# STM32F103RB.net
KiCad netlist of a schematic drawn in Altium Designer
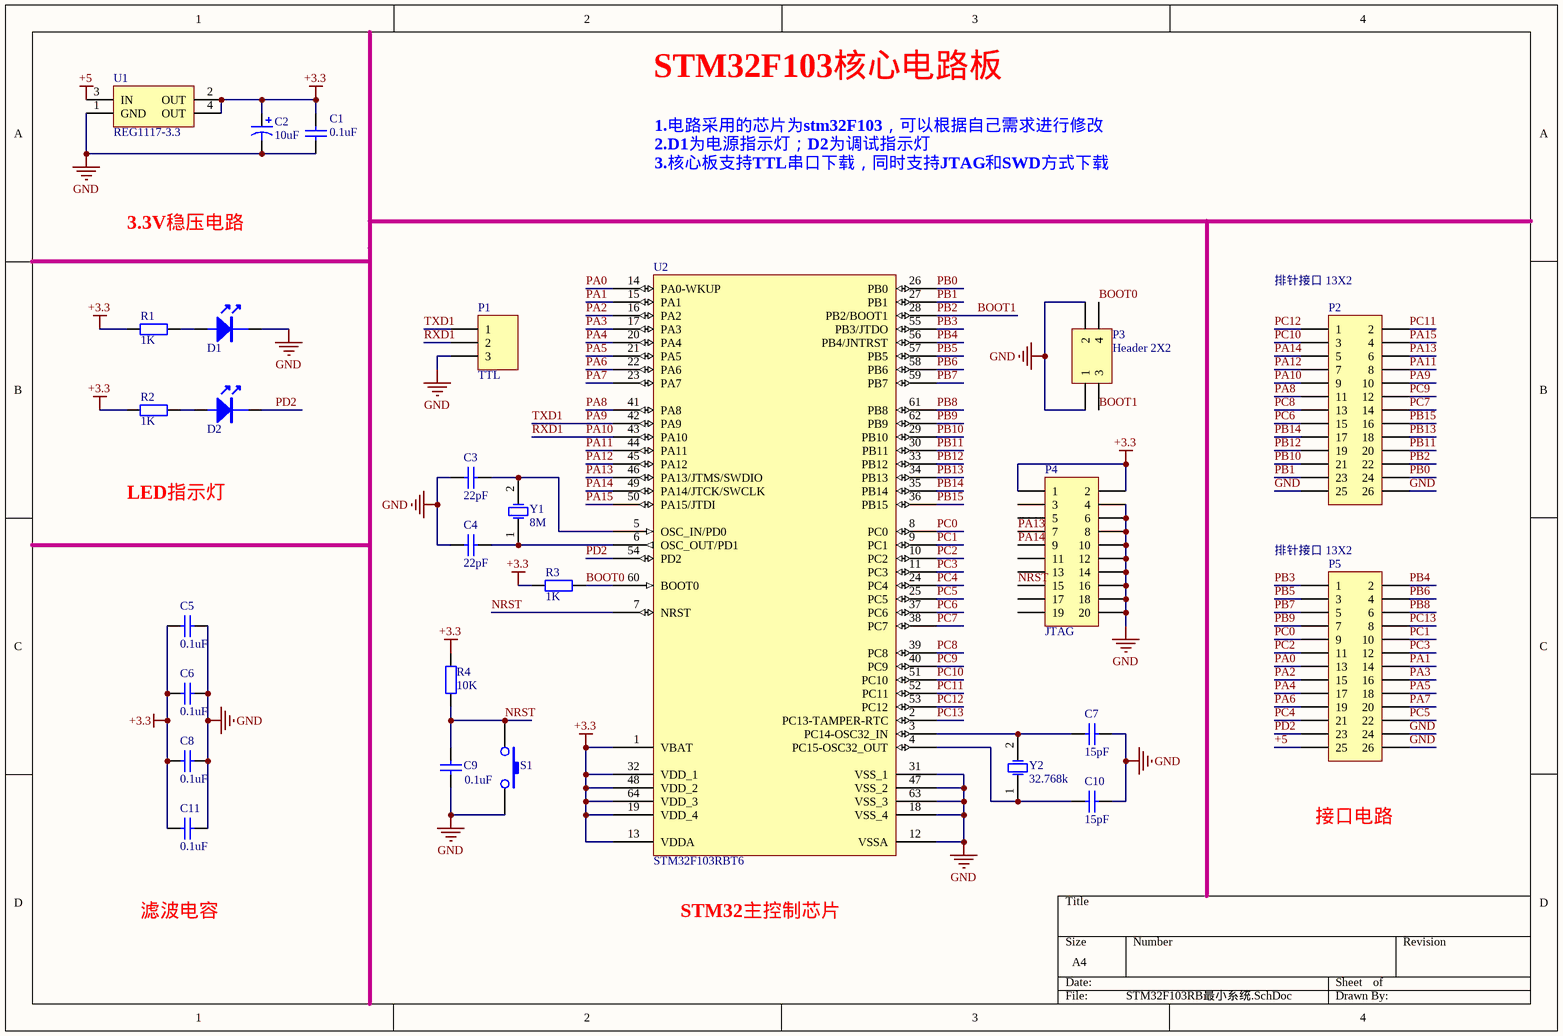
[diagram p0: STM32F103RB最小系统.SchDoc]

(export (version "E")
  (design (tool "Eeschema 10.0.6"))
  (components
    (comp (ref "C1")
      (value "0.1uF")
      (footprint "0805C")
      (description "Capacitor")
      (fields (field (name "PUBLISHER") "Altium Limited"))
      (libsource (lib "Miscellaneous Devices") (part "Cap"))
    )
    (comp (ref "C2")
      (value "10uF")
      (footprint "0805C")
      (description "Polarized Capacitor (Radial)")
      (fields (field (name "PUBLISHER") "Altium Limited"))
      (libsource (lib "Miscellaneous Devices") (part "Cap Pol1"))
    )
    (comp (ref "C3")
      (value "22pF")
      (footprint "0805C")
      (description "Capacitor")
      (fields (field (name "PUBLISHER") "Altium Limited"))
      (libsource (lib "Miscellaneous Devices") (part "Cap"))
    )
    (comp (ref "C4")
      (value "22pF")
      (footprint "0805C")
      (description "Capacitor")
      (fields (field (name "PUBLISHER") "Altium Limited"))
      (libsource (lib "Miscellaneous Devices") (part "Cap"))
    )
    (comp (ref "C5")
      (value "0.1uF")
      (footprint "0805C")
      (description "Capacitor")
      (fields (field (name "PUBLISHER") "Altium Limited"))
      (libsource (lib "Miscellaneous Devices") (part "Cap"))
    )
    (comp (ref "C6")
      (value "0.1uF")
      (footprint "0805C")
      (description "Capacitor")
      (fields (field (name "PUBLISHER") "Altium Limited"))
      (libsource (lib "Miscellaneous Devices") (part "Cap"))
    )
    (comp (ref "C7")
      (value "15pF")
      (footprint "0805C")
      (description "Capacitor")
      (fields (field (name "PUBLISHER") "Altium Limited"))
      (libsource (lib "Miscellaneous Devices") (part "Cap"))
    )
    (comp (ref "C8")
      (value "0.1uF")
      (footprint "0805C")
      (description "Capacitor")
      (fields (field (name "PUBLISHER") "Altium Limited"))
      (libsource (lib "Miscellaneous Devices") (part "Cap"))
    )
    (comp (ref "C9")
      (value "0.1uF")
      (footprint "0805C")
      (description "Capacitor")
      (fields (field (name "PUBLISHER") "Altium Limited"))
      (libsource (lib "Miscellaneous Devices") (part "Cap"))
    )
    (comp (ref "C10")
      (value "15pF")
      (footprint "0805C")
      (description "Capacitor")
      (fields (field (name "PUBLISHER") "Altium Limited"))
      (libsource (lib "Miscellaneous Devices") (part "Cap"))
    )
    (comp (ref "C11")
      (value "0.1uF")
      (footprint "0805C")
      (description "Capacitor")
      (fields (field (name "PUBLISHER") "Altium Limited"))
      (libsource (lib "Miscellaneous Devices") (part "Cap"))
    )
    (comp (ref "D1") (value "LED") (footprint "LED0805") (libsource (lib "CCDXPLIB") (part "LED")))
    (comp (ref "D2") (value "LED") (footprint "LED0805") (libsource (lib "CCDXPLIB") (part "LED")))
    (comp (ref "P1")
      (value "TTL")
      (footprint "HDR1X3")
      (description "Header, 3-Pin")
      (fields (field (name "PUBLISHER") "Altium Limited"))
      (libsource (lib "Miscellaneous Connectors") (part "Header 3"))
    )
    (comp (ref "P2")
      (value "排针接口 13X2")
      (footprint "HDR2X13")
      (description "Header, 13-Pin, Dual row")
      (fields (field (name "PUBLISHER") "Altium Limited"))
      (libsource (lib "Miscellaneous Connectors") (part "Header 13X2"))
    )
    (comp (ref "P3")
      (value "Header 2X2")
      (footprint "HDR2X2")
      (description "Header, 2-Pin, Dual row")
      (fields (field (name "PUBLISHER") "Altium Limited"))
      (libsource (lib "Miscellaneous Connectors") (part "Header 2X2"))
    )
    (comp (ref "P4")
      (value "JTAG")
      (footprint "JTAG20")
      (description "Header, 10-Pin, Dual row")
      (fields (field (name "PUBLISHER") "Altium Limited"))
      (libsource (lib "Miscellaneous Connectors") (part "Header 10X2"))
    )
    (comp (ref "P5")
      (value "排针接口 13X2")
      (footprint "HDR2X13")
      (description "Header, 13-Pin, Dual row")
      (fields (field (name "PUBLISHER") "Altium Limited"))
      (libsource (lib "Miscellaneous Connectors") (part "Header 13X2"))
    )
    (comp (ref "R1")
      (value "1K")
      (footprint "0805R")
      (description "Resistor")
      (fields (field (name "PUBLISHER") "Altium Limited"))
      (libsource (lib "Miscellaneous Devices") (part "Res2"))
    )
    (comp (ref "R2")
      (value "1K")
      (footprint "0805R")
      (description "Resistor")
      (fields (field (name "PUBLISHER") "Altium Limited"))
      (libsource (lib "Miscellaneous Devices") (part "Res2"))
    )
    (comp (ref "R3")
      (value "1K")
      (footprint "0805R")
      (description "Resistor")
      (fields (field (name "PUBLISHER") "Altium Limited"))
      (libsource (lib "Miscellaneous Devices") (part "Res2"))
    )
    (comp (ref "R4")
      (value "10K")
      (footprint "0805R")
      (description "Resistor")
      (fields (field (name "PUBLISHER") "Altium Limited"))
      (libsource (lib "") (part "Res2_1"))
    )
    (comp (ref "S1") (value "KEY") (footprint "KEY_SOP") (libsource (lib "CCDXPLIB") (part "KEY")))
    (comp (ref "U1")
      (value "REG1117-3.3")
      (footprint "ZZ311")
      (description "800mA and 1A Low Dropout Positive Regulator 2.85V, 3.3V, 5V, and Adjustable")
      (fields (field (name "PUBLISHER") "Altium Limited"))
      (libsource (lib "BB Power Mgt Voltage Regulator") (part "REG1117-3.3"))
    )
    (comp (ref "U2")
      (value "STM32F103RBT6")
      (footprint "LQFP64_N")
      (description "STM32 ARM-based 32-bit MCU with 128 Kbytes Flash, 64-pin LQFP, Industrial Temperature")
      (fields (field (name "PUBLISHER") "Altium Limited"))
      (libsource (lib "ST Microcontroller 32-Bit STM32") (part "STM32F103RBT6"))
    )
    (comp (ref "Y1")
      (value "8M")
      (footprint "OSC2PR-1")
      (description "Crystal Oscillator")
      (fields (field (name "PUBLISHER") "Altium Limited"))
      (libsource (lib "Miscellaneous Devices") (part "XTAL"))
    )
    (comp (ref "Y2")
      (value "32.768k")
      (footprint "XTAL-B")
      (description "Crystal Oscillator")
      (fields (field (name "PUBLISHER") "Altium Limited"))
      (libsource (lib "Miscellaneous Devices") (part "XTAL"))
    )
  )
  (nets
    (net (code "1") (name "+3.3") (class "Default")
      (node (ref "C1") (pin "2") (pinfunction "2_2") (pintype "passive"))
      (node (ref "C11") (pin "1") (pinfunction "1_1") (pintype "passive"))
      (node (ref "C2") (pin "1") (pinfunction "1_1") (pintype "passive"))
      (node (ref "C5") (pin "1") (pinfunction "1_1") (pintype "passive"))
      (node (ref "C6") (pin "1") (pinfunction "1_1") (pintype "passive"))
      (node (ref "C8") (pin "1") (pinfunction "1_1") (pintype "passive"))
      (node (ref "P4") (pin "1") (pinfunction "1_1") (pintype "passive"))
      (node (ref "P4") (pin "2") (pinfunction "2_2") (pintype "passive"))
      (node (ref "R1") (pin "1") (pinfunction "1_1") (pintype "passive"))
      (node (ref "R2") (pin "1") (pinfunction "1_1") (pintype "passive"))
      (node (ref "R3") (pin "1") (pinfunction "1_1") (pintype "passive"))
      (node (ref "R4") (pin "2") (pinfunction "2_2") (pintype "passive"))
      (node (ref "U1") (pin "2") (pinfunction "OUT_2") (pintype "power_in"))
      (node (ref "U1") (pin "4") (pinfunction "OUT_4") (pintype "power_in"))
      (node (ref "U2") (pin "1") (pinfunction "VBAT_1") (pintype "power_in"))
      (node (ref "U2") (pin "13") (pinfunction "VDDA_13") (pintype "power_in"))
      (node (ref "U2") (pin "19") (pinfunction "VDD_4_19") (pintype "power_in"))
      (node (ref "U2") (pin "32") (pinfunction "VDD_1_32") (pintype "power_in"))
      (node (ref "U2") (pin "48") (pinfunction "VDD_2_48") (pintype "power_in"))
      (node (ref "U2") (pin "64") (pinfunction "VDD_3_64") (pintype "power_in"))
    )
    (net (code "2") (name "+5") (class "Default")
      (node (ref "P5") (pin "25") (pinfunction "25_25") (pintype "passive"))
      (node (ref "U1") (pin "3") (pinfunction "IN_3") (pintype "power_in"))
    )
    (net (code "3") (name "/BOOT0") (class "Default")
      (node (ref "P3") (pin "4") (pinfunction "4_4") (pintype "passive"))
      (node (ref "R3") (pin "2") (pinfunction "2_2") (pintype "passive"))
      (node (ref "U2") (pin "60") (pinfunction "BOOT0_60") (pintype "input"))
    )
    (net (code "4") (name "/BOOT1") (class "Default")
      (node (ref "P2") (pin "22") (pinfunction "22_22") (pintype "passive"))
      (node (ref "P3") (pin "3") (pinfunction "3_3") (pintype "passive"))
      (node (ref "U2") (pin "28") (pinfunction "PB2/BOOT1_28") (pintype "bidirectional"))
    )
    (net (code "5") (name "/NRST") (class "Default")
      (node (ref "C9") (pin "2") (pinfunction "2_2") (pintype "passive"))
      (node (ref "P4") (pin "15") (pinfunction "15_15") (pintype "passive"))
      (node (ref "R4") (pin "1") (pinfunction "1_1") (pintype "passive"))
      (node (ref "S1") (pin "1") (pinfunction "1_1") (pintype "passive"))
      (node (ref "U2") (pin "7") (pinfunction "NRST_7") (pintype "bidirectional"))
    )
    (net (code "6") (name "/PA0") (class "Default")
      (node (ref "P5") (pin "13") (pinfunction "13_13") (pintype "passive"))
      (node (ref "U2") (pin "14") (pinfunction "PA0-WKUP_14") (pintype "bidirectional"))
    )
    (net (code "7") (name "/PA1") (class "Default")
      (node (ref "P5") (pin "14") (pinfunction "14_14") (pintype "passive"))
      (node (ref "U2") (pin "15") (pinfunction "PA1_15") (pintype "bidirectional"))
    )
    (net (code "8") (name "/PA2") (class "Default")
      (node (ref "P5") (pin "15") (pinfunction "15_15") (pintype "passive"))
      (node (ref "U2") (pin "16") (pinfunction "PA2_16") (pintype "bidirectional"))
    )
    (net (code "9") (name "/PA3") (class "Default")
      (node (ref "P5") (pin "16") (pinfunction "16_16") (pintype "passive"))
      (node (ref "U2") (pin "17") (pinfunction "PA3_17") (pintype "bidirectional"))
    )
    (net (code "10") (name "/PA4") (class "Default")
      (node (ref "P5") (pin "17") (pinfunction "17_17") (pintype "passive"))
      (node (ref "U2") (pin "20") (pinfunction "PA4_20") (pintype "bidirectional"))
    )
    (net (code "11") (name "/PA5") (class "Default")
      (node (ref "P5") (pin "18") (pinfunction "18_18") (pintype "passive"))
      (node (ref "U2") (pin "21") (pinfunction "PA5_21") (pintype "bidirectional"))
    )
    (net (code "12") (name "/PA6") (class "Default")
      (node (ref "P5") (pin "19") (pinfunction "19_19") (pintype "passive"))
      (node (ref "U2") (pin "22") (pinfunction "PA6_22") (pintype "bidirectional"))
    )
    (net (code "13") (name "/PA7") (class "Default")
      (node (ref "P5") (pin "20") (pinfunction "20_20") (pintype "passive"))
      (node (ref "U2") (pin "23") (pinfunction "PA7_23") (pintype "bidirectional"))
    )
    (net (code "14") (name "/PA8") (class "Default")
      (node (ref "P2") (pin "11") (pinfunction "11_11") (pintype "passive"))
      (node (ref "U2") (pin "41") (pinfunction "PA8_41") (pintype "bidirectional"))
    )
    (net (code "15") (name "/PA9") (class "Default")
      (node (ref "P1") (pin "1") (pinfunction "1_1") (pintype "passive"))
      (node (ref "P2") (pin "10") (pinfunction "10_10") (pintype "passive"))
      (node (ref "U2") (pin "42") (pinfunction "PA9_42") (pintype "bidirectional"))
    )
    (net (code "16") (name "/PA10") (class "Default")
      (node (ref "P1") (pin "2") (pinfunction "2_2") (pintype "passive"))
      (node (ref "P2") (pin "9") (pinfunction "9_9") (pintype "passive"))
      (node (ref "U2") (pin "43") (pinfunction "PA10_43") (pintype "bidirectional"))
    )
    (net (code "17") (name "/PA11") (class "Default")
      (node (ref "P2") (pin "8") (pinfunction "8_8") (pintype "passive"))
      (node (ref "U2") (pin "44") (pinfunction "PA11_44") (pintype "bidirectional"))
    )
    (net (code "18") (name "/PA12") (class "Default")
      (node (ref "P2") (pin "7") (pinfunction "7_7") (pintype "passive"))
      (node (ref "U2") (pin "45") (pinfunction "PA12_45") (pintype "bidirectional"))
    )
    (net (code "19") (name "/PA13") (class "Default")
      (node (ref "P2") (pin "6") (pinfunction "6_6") (pintype "passive"))
      (node (ref "P4") (pin "7") (pinfunction "7_7") (pintype "passive"))
      (node (ref "U2") (pin "46") (pinfunction "PA13/JTMS/SWDIO_46") (pintype "bidirectional"))
    )
    (net (code "20") (name "/PA14") (class "Default")
      (node (ref "P2") (pin "5") (pinfunction "5_5") (pintype "passive"))
      (node (ref "P4") (pin "9") (pinfunction "9_9") (pintype "passive"))
      (node (ref "U2") (pin "49") (pinfunction "PA14/JTCK/SWCLK_49") (pintype "bidirectional"))
    )
    (net (code "21") (name "/PA15") (class "Default")
      (node (ref "P2") (pin "4") (pinfunction "4_4") (pintype "passive"))
      (node (ref "U2") (pin "50") (pinfunction "PA15/JTDI_50") (pintype "bidirectional"))
    )
    (net (code "22") (name "/PB0") (class "Default")
      (node (ref "P2") (pin "24") (pinfunction "24_24") (pintype "passive"))
      (node (ref "U2") (pin "26") (pinfunction "PB0_26") (pintype "bidirectional"))
    )
    (net (code "23") (name "/PB1") (class "Default")
      (node (ref "P2") (pin "23") (pinfunction "23_23") (pintype "passive"))
      (node (ref "U2") (pin "27") (pinfunction "PB1_27") (pintype "bidirectional"))
    )
    (net (code "24") (name "/PB3") (class "Default")
      (node (ref "P5") (pin "1") (pinfunction "1_1") (pintype "passive"))
      (node (ref "U2") (pin "55") (pinfunction "PB3/JTDO_55") (pintype "bidirectional"))
    )
    (net (code "25") (name "/PB4") (class "Default")
      (node (ref "P5") (pin "2") (pinfunction "2_2") (pintype "passive"))
      (node (ref "U2") (pin "56") (pinfunction "PB4/JNTRST_56") (pintype "bidirectional"))
    )
    (net (code "26") (name "/PB5") (class "Default")
      (node (ref "P5") (pin "3") (pinfunction "3_3") (pintype "passive"))
      (node (ref "U2") (pin "57") (pinfunction "PB5_57") (pintype "bidirectional"))
    )
    (net (code "27") (name "/PB6") (class "Default")
      (node (ref "P5") (pin "4") (pinfunction "4_4") (pintype "passive"))
      (node (ref "U2") (pin "58") (pinfunction "PB6_58") (pintype "bidirectional"))
    )
    (net (code "28") (name "/PB7") (class "Default")
      (node (ref "P5") (pin "5") (pinfunction "5_5") (pintype "passive"))
      (node (ref "U2") (pin "59") (pinfunction "PB7_59") (pintype "bidirectional"))
    )
    (net (code "29") (name "/PB8") (class "Default")
      (node (ref "P5") (pin "6") (pinfunction "6_6") (pintype "passive"))
      (node (ref "U2") (pin "61") (pinfunction "PB8_61") (pintype "bidirectional"))
    )
    (net (code "30") (name "/PB9") (class "Default")
      (node (ref "P5") (pin "7") (pinfunction "7_7") (pintype "passive"))
      (node (ref "U2") (pin "62") (pinfunction "PB9_62") (pintype "bidirectional"))
    )
    (net (code "31") (name "/PB10") (class "Default")
      (node (ref "P2") (pin "21") (pinfunction "21_21") (pintype "passive"))
      (node (ref "U2") (pin "29") (pinfunction "PB10_29") (pintype "bidirectional"))
    )
    (net (code "32") (name "/PB11") (class "Default")
      (node (ref "P2") (pin "20") (pinfunction "20_20") (pintype "passive"))
      (node (ref "U2") (pin "30") (pinfunction "PB11_30") (pintype "bidirectional"))
    )
    (net (code "33") (name "/PB12") (class "Default")
      (node (ref "P2") (pin "19") (pinfunction "19_19") (pintype "passive"))
      (node (ref "U2") (pin "33") (pinfunction "PB12_33") (pintype "bidirectional"))
    )
    (net (code "34") (name "/PB13") (class "Default")
      (node (ref "P2") (pin "18") (pinfunction "18_18") (pintype "passive"))
      (node (ref "U2") (pin "34") (pinfunction "PB13_34") (pintype "bidirectional"))
    )
    (net (code "35") (name "/PB14") (class "Default")
      (node (ref "P2") (pin "17") (pinfunction "17_17") (pintype "passive"))
      (node (ref "U2") (pin "35") (pinfunction "PB14_35") (pintype "bidirectional"))
    )
    (net (code "36") (name "/PB15") (class "Default")
      (node (ref "P2") (pin "16") (pinfunction "16_16") (pintype "passive"))
      (node (ref "U2") (pin "36") (pinfunction "PB15_36") (pintype "bidirectional"))
    )
    (net (code "37") (name "/PC0") (class "Default")
      (node (ref "P5") (pin "9") (pinfunction "9_9") (pintype "passive"))
      (node (ref "U2") (pin "8") (pinfunction "PC0_8") (pintype "bidirectional"))
    )
    (net (code "38") (name "/PC1") (class "Default")
      (node (ref "P5") (pin "10") (pinfunction "10_10") (pintype "passive"))
      (node (ref "U2") (pin "9") (pinfunction "PC1_9") (pintype "bidirectional"))
    )
    (net (code "39") (name "/PC2") (class "Default")
      (node (ref "P5") (pin "11") (pinfunction "11_11") (pintype "passive"))
      (node (ref "U2") (pin "10") (pinfunction "PC2_10") (pintype "bidirectional"))
    )
    (net (code "40") (name "/PC3") (class "Default")
      (node (ref "P5") (pin "12") (pinfunction "12_12") (pintype "passive"))
      (node (ref "U2") (pin "11") (pinfunction "PC3_11") (pintype "bidirectional"))
    )
    (net (code "41") (name "/PC4") (class "Default")
      (node (ref "P5") (pin "21") (pinfunction "21_21") (pintype "passive"))
      (node (ref "U2") (pin "24") (pinfunction "PC4_24") (pintype "bidirectional"))
    )
    (net (code "42") (name "/PC5") (class "Default")
      (node (ref "P5") (pin "22") (pinfunction "22_22") (pintype "passive"))
      (node (ref "U2") (pin "25") (pinfunction "PC5_25") (pintype "bidirectional"))
    )
    (net (code "43") (name "/PC6") (class "Default")
      (node (ref "P2") (pin "15") (pinfunction "15_15") (pintype "passive"))
      (node (ref "U2") (pin "37") (pinfunction "PC6_37") (pintype "bidirectional"))
    )
    (net (code "44") (name "/PC7") (class "Default")
      (node (ref "P2") (pin "14") (pinfunction "14_14") (pintype "passive"))
      (node (ref "U2") (pin "38") (pinfunction "PC7_38") (pintype "bidirectional"))
    )
    (net (code "45") (name "/PC8") (class "Default")
      (node (ref "P2") (pin "13") (pinfunction "13_13") (pintype "passive"))
      (node (ref "U2") (pin "39") (pinfunction "PC8_39") (pintype "bidirectional"))
    )
    (net (code "46") (name "/PC9") (class "Default")
      (node (ref "P2") (pin "12") (pinfunction "12_12") (pintype "passive"))
      (node (ref "U2") (pin "40") (pinfunction "PC9_40") (pintype "bidirectional"))
    )
    (net (code "47") (name "/PC10") (class "Default")
      (node (ref "P2") (pin "3") (pinfunction "3_3") (pintype "passive"))
      (node (ref "U2") (pin "51") (pinfunction "PC10_51") (pintype "bidirectional"))
    )
    (net (code "48") (name "/PC11") (class "Default")
      (node (ref "P2") (pin "2") (pinfunction "2_2") (pintype "passive"))
      (node (ref "U2") (pin "52") (pinfunction "PC11_52") (pintype "bidirectional"))
    )
    (net (code "49") (name "/PC12") (class "Default")
      (node (ref "P2") (pin "1") (pinfunction "1_1") (pintype "passive"))
      (node (ref "U2") (pin "53") (pinfunction "PC12_53") (pintype "bidirectional"))
    )
    (net (code "50") (name "/PC13") (class "Default")
      (node (ref "P5") (pin "8") (pinfunction "8_8") (pintype "passive"))
      (node (ref "U2") (pin "2") (pinfunction "PC13-TAMPER-RTC_2") (pintype "bidirectional"))
    )
    (net (code "51") (name "/PD2") (class "Default")
      (node (ref "D2") (pin "2") (pinfunction "2_2") (pintype "passive"))
      (node (ref "P5") (pin "23") (pinfunction "23_23") (pintype "passive"))
      (node (ref "U2") (pin "54") (pinfunction "PD2_54") (pintype "bidirectional"))
    )
    (net (code "52") (name "GND") (class "Default")
      (node (ref "C1") (pin "1") (pinfunction "1_1") (pintype "passive"))
      (node (ref "C10") (pin "2") (pinfunction "2_2") (pintype "passive"))
      (node (ref "C11") (pin "2") (pinfunction "2_2") (pintype "passive"))
      (node (ref "C2") (pin "2") (pinfunction "2_2") (pintype "passive"))
      (node (ref "C3") (pin "1") (pinfunction "1_1") (pintype "passive"))
      (node (ref "C4") (pin "1") (pinfunction "1_1") (pintype "passive"))
      (node (ref "C5") (pin "2") (pinfunction "2_2") (pintype "passive"))
      (node (ref "C6") (pin "2") (pinfunction "2_2") (pintype "passive"))
      (node (ref "C7") (pin "2") (pinfunction "2_2") (pintype "passive"))
      (node (ref "C8") (pin "2") (pinfunction "2_2") (pintype "passive"))
      (node (ref "C9") (pin "1") (pinfunction "1_1") (pintype "passive"))
      (node (ref "D1") (pin "2") (pinfunction "2_2") (pintype "passive"))
      (node (ref "P1") (pin "3") (pinfunction "3_3") (pintype "passive"))
      (node (ref "P2") (pin "25") (pinfunction "25_25") (pintype "passive"))
      (node (ref "P2") (pin "26") (pinfunction "26_26") (pintype "passive"))
      (node (ref "P3") (pin "1") (pinfunction "1_1") (pintype "passive"))
      (node (ref "P3") (pin "2") (pinfunction "2_2") (pintype "passive"))
      (node (ref "P4") (pin "10") (pinfunction "10_10") (pintype "passive"))
      (node (ref "P4") (pin "12") (pinfunction "12_12") (pintype "passive"))
      (node (ref "P4") (pin "14") (pinfunction "14_14") (pintype "passive"))
      (node (ref "P4") (pin "16") (pinfunction "16_16") (pintype "passive"))
      (node (ref "P4") (pin "18") (pinfunction "18_18") (pintype "passive"))
      (node (ref "P4") (pin "20") (pinfunction "20_20") (pintype "passive"))
      (node (ref "P4") (pin "4") (pinfunction "4_4") (pintype "passive"))
      (node (ref "P4") (pin "6") (pinfunction "6_6") (pintype "passive"))
      (node (ref "P4") (pin "8") (pinfunction "8_8") (pintype "passive"))
      (node (ref "P5") (pin "24") (pinfunction "24_24") (pintype "passive"))
      (node (ref "P5") (pin "26") (pinfunction "26_26") (pintype "passive"))
      (node (ref "S1") (pin "2") (pinfunction "2_2") (pintype "passive"))
      (node (ref "U1") (pin "1") (pinfunction "GND_1") (pintype "power_in"))
      (node (ref "U2") (pin "12") (pinfunction "VSSA_12") (pintype "power_in"))
      (node (ref "U2") (pin "18") (pinfunction "VSS_4_18") (pintype "power_in"))
      (node (ref "U2") (pin "31") (pinfunction "VSS_1_31") (pintype "power_in"))
      (node (ref "U2") (pin "47") (pinfunction "VSS_2_47") (pintype "power_in"))
      (node (ref "U2") (pin "63") (pinfunction "VSS_3_63") (pintype "power_in"))
    )
    (net (code "53") (name "Net-(D1-Pad1)") (class "Default")
      (node (ref "D1") (pin "1") (pinfunction "1_1") (pintype "passive"))
      (node (ref "R1") (pin "2") (pinfunction "2_2") (pintype "passive"))
    )
    (net (code "54") (name "Net-(D2-Pad1)") (class "Default")
      (node (ref "D2") (pin "1") (pinfunction "1_1") (pintype "passive"))
      (node (ref "R2") (pin "2") (pinfunction "2_2") (pintype "passive"))
    )
    (net (code "55") (name "Net-(U2-OSC_IN{slash}PD0)") (class "Default")
      (node (ref "C3") (pin "2") (pinfunction "2_2") (pintype "passive"))
      (node (ref "U2") (pin "5") (pinfunction "OSC_IN/PD0_5") (pintype "input"))
      (node (ref "Y1") (pin "2") (pinfunction "OSC2_2") (pintype "passive"))
    )
    (net (code "56") (name "Net-(U2-OSC_OUT{slash}PD1)") (class "Default")
      (node (ref "C4") (pin "2") (pinfunction "2_2") (pintype "passive"))
      (node (ref "U2") (pin "6") (pinfunction "OSC_OUT/PD1_6") (pintype "output"))
      (node (ref "Y1") (pin "1") (pinfunction "OSC1_1") (pintype "passive"))
    )
    (net (code "57") (name "Net-(U2-PC14-OSC32_IN)") (class "Default")
      (node (ref "C7") (pin "1") (pinfunction "1_1") (pintype "passive"))
      (node (ref "U2") (pin "3") (pinfunction "PC14-OSC32_IN_3") (pintype "bidirectional"))
      (node (ref "Y2") (pin "2") (pinfunction "OSC2_2") (pintype "passive"))
    )
    (net (code "58") (name "Net-(U2-PC15-OSC32_OUT)") (class "Default")
      (node (ref "C10") (pin "1") (pinfunction "1_1") (pintype "passive"))
      (node (ref "U2") (pin "4") (pinfunction "PC15-OSC32_OUT_4") (pintype "bidirectional"))
      (node (ref "Y2") (pin "1") (pinfunction "OSC1_1") (pintype "passive"))
    )
    (net (code "59") (name "unconnected-(P4-Pad3)") (class "Default")
      (node (ref "P4") (pin "3") (pinfunction "3_3") (pintype "passive"))
    )
    (net (code "60") (name "unconnected-(P4-Pad5)") (class "Default")
      (node (ref "P4") (pin "5") (pinfunction "5_5") (pintype "passive"))
    )
    (net (code "61") (name "unconnected-(P4-Pad11)") (class "Default")
      (node (ref "P4") (pin "11") (pinfunction "11_11") (pintype "passive"))
    )
    (net (code "62") (name "unconnected-(P4-Pad13)") (class "Default")
      (node (ref "P4") (pin "13") (pinfunction "13_13") (pintype "passive"))
    )
    (net (code "63") (name "unconnected-(P4-Pad17)") (class "Default")
      (node (ref "P4") (pin "17") (pinfunction "17_17") (pintype "passive"))
    )
    (net (code "64") (name "unconnected-(P4-Pad19)") (class "Default")
      (node (ref "P4") (pin "19") (pinfunction "19_19") (pintype "passive"))
    )
  )
)
